# Soapbox_of.net
KiCad netlist of a schematic drawn in EAGLE
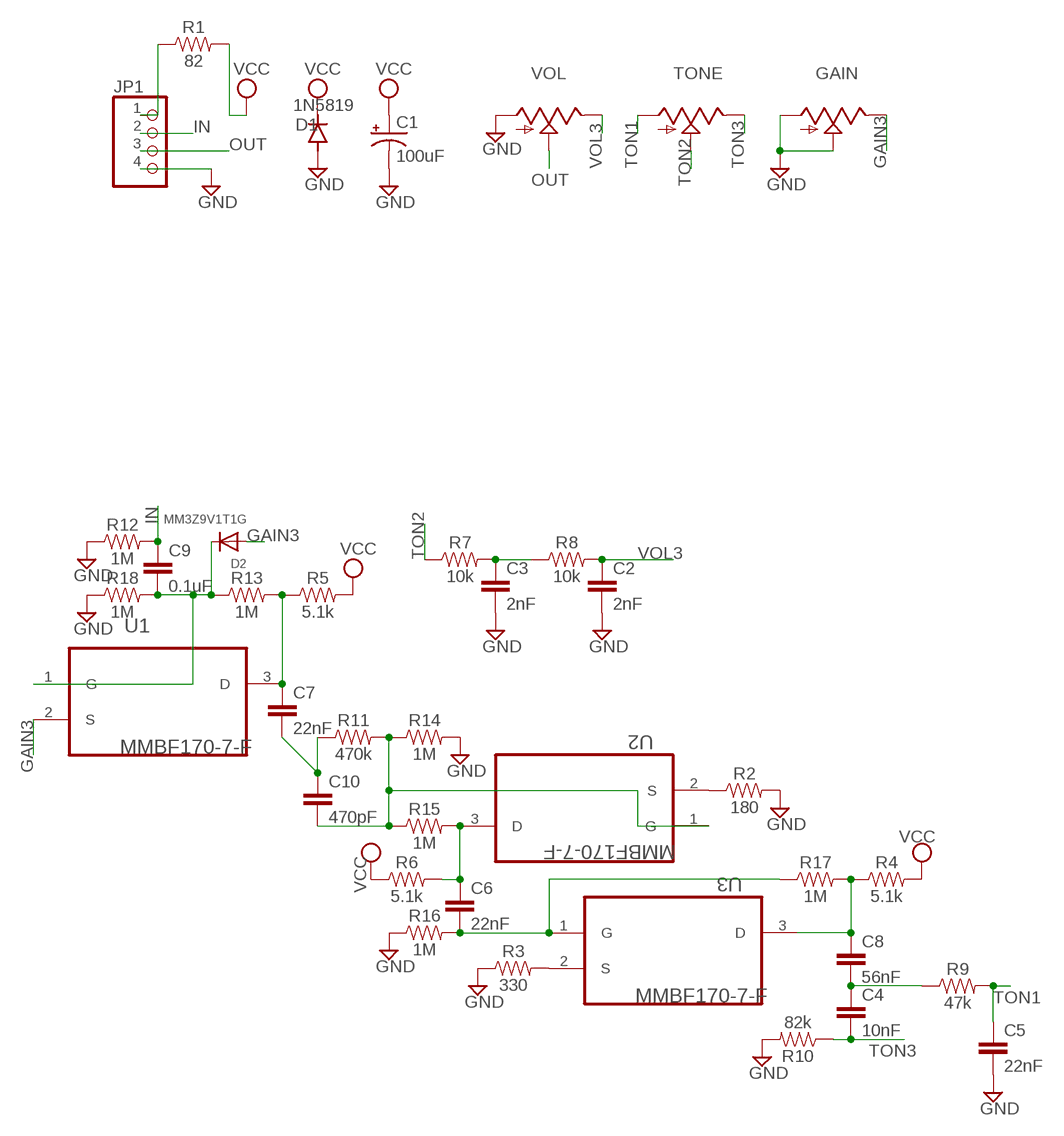
[diagram p0: schematic, sheet 1]

(export (version "E")
  (design (tool "Eeschema 10.0.6"))
  (components
    (comp (ref "C1")
      (value "100uF")
      (footprint "eagle-import:PAN_B_SMD+THRU")
      (libsource (lib "eagle-import") (part "CAP_SMD+THRUPAN_B"))
    )
    (comp (ref "C2")
      (value "2nF")
      (footprint "eagle-import:0603")
      (libsource (lib "eagle-import") (part "2.2NF/2200PF-0603-50V-10%"))
    )
    (comp (ref "C3")
      (value "2nF")
      (footprint "eagle-import:0603")
      (libsource (lib "eagle-import") (part "2.2NF/2200PF-0603-50V-10%"))
    )
    (comp (ref "C4")
      (value "10nF")
      (footprint "eagle-import:0603")
      (libsource (lib "eagle-import") (part "10NF-0603-50V-10%"))
    )
    (comp (ref "C5")
      (value "22nF")
      (footprint "eagle-import:0603")
      (libsource (lib "eagle-import") (part "22NF/22,000PF-0603-50V-10%"))
    )
    (comp (ref "C6")
      (value "22nF")
      (footprint "eagle-import:0603")
      (libsource (lib "eagle-import") (part "22NF/22,000PF-0603-50V-10%"))
    )
    (comp (ref "C7")
      (value "22nF")
      (footprint "eagle-import:0603")
      (libsource (lib "eagle-import") (part "22NF/22,000PF-0603-50V-10%"))
    )
    (comp (ref "C8")
      (value "56nF")
      (footprint "eagle-import:0603")
      (libsource (lib "eagle-import") (part "47NF-0603-25V-5%"))
    )
    (comp (ref "C9")
      (value "0.1uF")
      (footprint "eagle-import:0603")
      (libsource (lib "eagle-import") (part "0.1UF-0603-25V-(+80/-20%)"))
    )
    (comp (ref "C10")
      (value "470pF")
      (footprint "eagle-import:0603")
      (libsource (lib "eagle-import") (part "470PF-0603-50V-5%"))
    )
    (comp (ref "D1")
      (value "1N5819")
      (footprint "eagle-import:SOD123")
      (libsource (lib "eagle-import") (part "DIODE-SOD123"))
    )
    (comp (ref "D2")
      (value "MM3Z9V1T1G")
      (footprint "eagle-import:SOD-323F")
      (libsource (lib "eagle-import") (part "DIODESOD-323F"))
    )
    (comp (ref "GAIN")
      (value "9MM_SNAP-IN_POT_")
      (footprint "eagle-import:9MM_SNAP-IN_POT")
      (libsource (lib "eagle-import") (part "9MM_SNAP-IN_POT_"))
    )
    (comp (ref "JP1")
      (value "PINHD-1X4")
      (footprint "eagle-import:1X04")
      (libsource (lib "eagle-import") (part "PINHD-1X4"))
    )
    (comp (ref "R1")
      (value "82")
      (footprint "eagle-import:0603")
      (libsource (lib "eagle-import") (part "82OHM-0603-1/10W-1%"))
    )
    (comp (ref "R2")
      (value "180")
      (footprint "eagle-import:0603")
      (libsource (lib "eagle-import") (part "180OHM-0603-1/10W-1%"))
    )
    (comp (ref "R3")
      (value "330")
      (footprint "eagle-import:0603")
      (libsource (lib "eagle-import") (part "330OHM-0603-1/10W-1%"))
    )
    (comp (ref "R4")
      (value "5.1k")
      (footprint "eagle-import:0603")
      (libsource (lib "eagle-import") (part "5.6KOHM-0603-1/10W-1%"))
    )
    (comp (ref "R5")
      (value "5.1k")
      (footprint "eagle-import:0603")
      (libsource (lib "eagle-import") (part "5.6KOHM-0603-1/10W-1%"))
    )
    (comp (ref "R6")
      (value "5.1k")
      (footprint "eagle-import:0603")
      (libsource (lib "eagle-import") (part "5.6KOHM-0603-1/10W-1%"))
    )
    (comp (ref "R7")
      (value "10k")
      (footprint "eagle-import:0603")
      (libsource (lib "eagle-import") (part "10KOHM-0603-1/10W-1%"))
    )
    (comp (ref "R8")
      (value "10k")
      (footprint "eagle-import:0603")
      (libsource (lib "eagle-import") (part "10KOHM-0603-1/10W-1%"))
    )
    (comp (ref "R9")
      (value "47k")
      (footprint "eagle-import:0603")
      (libsource (lib "eagle-import") (part "47KOHM-0603-1/10W-1%"))
    )
    (comp (ref "R10")
      (value "82k")
      (footprint "eagle-import:0603")
      (libsource (lib "eagle-import") (part "82OHM-0603-1/10W-1%"))
    )
    (comp (ref "R11")
      (value "470k")
      (footprint "eagle-import:0603")
      (libsource (lib "eagle-import") (part "470OHM-0603-1/10W-1%"))
    )
    (comp (ref "R12")
      (value "1M")
      (footprint "eagle-import:0603")
      (libsource (lib "eagle-import") (part "1MOHM-0603-1/4W-5%"))
    )
    (comp (ref "R13")
      (value "1M")
      (footprint "eagle-import:0603")
      (libsource (lib "eagle-import") (part "1MOHM-0603-1/4W-5%"))
    )
    (comp (ref "R14")
      (value "1M")
      (footprint "eagle-import:0603")
      (libsource (lib "eagle-import") (part "1MOHM-0603-1/4W-5%"))
    )
    (comp (ref "R15")
      (value "1M")
      (footprint "eagle-import:0603")
      (libsource (lib "eagle-import") (part "1MOHM-0603-1/4W-5%"))
    )
    (comp (ref "R16")
      (value "1M")
      (footprint "eagle-import:0603")
      (libsource (lib "eagle-import") (part "1MOHM-0603-1/4W-5%"))
    )
    (comp (ref "R17")
      (value "1M")
      (footprint "eagle-import:0603")
      (libsource (lib "eagle-import") (part "1MOHM-0603-1/4W-5%"))
    )
    (comp (ref "R18")
      (value "1M")
      (footprint "eagle-import:0603")
      (libsource (lib "eagle-import") (part "1MOHM-0603-1/4W-5%"))
    )
    (comp (ref "TONE")
      (value "9MM_SNAP-IN_POT_")
      (footprint "eagle-import:9MM_SNAP-IN_POT")
      (libsource (lib "eagle-import") (part "9MM_SNAP-IN_POT_"))
    )
    (comp (ref "U1")
      (value "MMBF170-7-F")
      (footprint "eagle-import:SOT103P240X110-3N")
      (fields (field (name "MF") "Diodes Inc."))
      (libsource (lib "eagle-import") (part "MMBF170-7-F"))
    )
    (comp (ref "U2")
      (value "MMBF170-7-F")
      (footprint "eagle-import:SOT103P240X110-3N")
      (fields (field (name "MF") "Diodes Inc."))
      (libsource (lib "eagle-import") (part "MMBF170-7-F"))
    )
    (comp (ref "U3")
      (value "MMBF170-7-F")
      (footprint "eagle-import:SOT103P240X110-3N")
      (fields (field (name "MF") "Diodes Inc."))
      (libsource (lib "eagle-import") (part "MMBF170-7-F"))
    )
    (comp (ref "VOL")
      (value "9MM_SNAP-IN_POT_")
      (footprint "eagle-import:9MM_SNAP-IN_POT")
      (libsource (lib "eagle-import") (part "9MM_SNAP-IN_POT_"))
    )
  )
  (nets
    (net (code "1") (name "/GAIN3") (class "Default")
      (node (ref "D2") (pin "A") (pinfunction "A_A") (pintype "passive"))
      (node (ref "GAIN") (pin "3") (pinfunction "E_3") (pintype "passive"))
      (node (ref "U1") (pin "2") (pinfunction "S_2") (pintype "passive"))
    )
    (net (code "2") (name "/IN") (class "Default")
      (node (ref "C9") (pin "1") (pinfunction "1_1") (pintype "passive"))
      (node (ref "JP1") (pin "2") (pinfunction "2_2") (pintype "passive"))
      (node (ref "R12") (pin "2") (pinfunction "2_2") (pintype "passive"))
    )
    (net (code "3") (name "/OUT") (class "Default")
      (node (ref "JP1") (pin "3") (pinfunction "3_3") (pintype "passive"))
      (node (ref "VOL") (pin "2") (pinfunction "S_2") (pintype "passive"))
    )
    (net (code "4") (name "/TON1") (class "Default")
      (node (ref "C5") (pin "1") (pinfunction "1_1") (pintype "passive"))
      (node (ref "R9") (pin "2") (pinfunction "2_2") (pintype "passive"))
      (node (ref "TONE") (pin "1") (pinfunction "A_1") (pintype "passive"))
    )
    (net (code "5") (name "/TON2") (class "Default")
      (node (ref "R7") (pin "1") (pinfunction "1_1") (pintype "passive"))
      (node (ref "TONE") (pin "2") (pinfunction "S_2") (pintype "passive"))
    )
    (net (code "6") (name "/TON3") (class "Default")
      (node (ref "C4") (pin "2") (pinfunction "2_2") (pintype "passive"))
      (node (ref "R10") (pin "1") (pinfunction "1_1") (pintype "passive"))
      (node (ref "TONE") (pin "3") (pinfunction "E_3") (pintype "passive"))
    )
    (net (code "7") (name "/VOL3") (class "Default")
      (node (ref "C2") (pin "1") (pinfunction "1_1") (pintype "passive"))
      (node (ref "R8") (pin "2") (pinfunction "2_2") (pintype "passive"))
      (node (ref "VOL") (pin "3") (pinfunction "E_3") (pintype "passive"))
    )
    (net (code "8") (name "GND") (class "Default")
      (node (ref "C1") (pin "-") (pinfunction "-_-") (pintype "passive"))
      (node (ref "C1") (pin "--") (pinfunction "-_--") (pintype "passive"))
      (node (ref "C2") (pin "2") (pinfunction "2_2") (pintype "passive"))
      (node (ref "C3") (pin "2") (pinfunction "2_2") (pintype "passive"))
      (node (ref "C5") (pin "2") (pinfunction "2_2") (pintype "passive"))
      (node (ref "D1") (pin "A") (pinfunction "A_A") (pintype "passive"))
      (node (ref "GAIN") (pin "1") (pinfunction "A_1") (pintype "passive"))
      (node (ref "GAIN") (pin "2") (pinfunction "S_2") (pintype "passive"))
      (node (ref "JP1") (pin "4") (pinfunction "4_4") (pintype "passive"))
      (node (ref "R10") (pin "2") (pinfunction "2_2") (pintype "passive"))
      (node (ref "R12") (pin "1") (pinfunction "1_1") (pintype "passive"))
      (node (ref "R14") (pin "2") (pinfunction "2_2") (pintype "passive"))
      (node (ref "R16") (pin "1") (pinfunction "1_1") (pintype "passive"))
      (node (ref "R18") (pin "1") (pinfunction "1_1") (pintype "passive"))
      (node (ref "R2") (pin "2") (pinfunction "2_2") (pintype "passive"))
      (node (ref "R3") (pin "1") (pinfunction "1_1") (pintype "passive"))
      (node (ref "VOL") (pin "1") (pinfunction "A_1") (pintype "passive"))
    )
    (net (code "9") (name "Net-(C3-Pad1)") (class "Default")
      (node (ref "C3") (pin "1") (pinfunction "1_1") (pintype "passive"))
      (node (ref "R7") (pin "2") (pinfunction "2_2") (pintype "passive"))
      (node (ref "R8") (pin "1") (pinfunction "1_1") (pintype "passive"))
    )
    (net (code "10") (name "Net-(C4-Pad1)") (class "Default")
      (node (ref "C4") (pin "1") (pinfunction "1_1") (pintype "passive"))
      (node (ref "C8") (pin "2") (pinfunction "2_2") (pintype "passive"))
      (node (ref "R9") (pin "1") (pinfunction "1_1") (pintype "passive"))
    )
    (net (code "11") (name "Net-(C10-Pad1)") (class "Default")
      (node (ref "C10") (pin "1") (pinfunction "1_1") (pintype "passive"))
      (node (ref "C7") (pin "2") (pinfunction "2_2") (pintype "passive"))
      (node (ref "R11") (pin "1") (pinfunction "1_1") (pintype "passive"))
    )
    (net (code "12") (name "Net-(JP1-Pad1)") (class "Default")
      (node (ref "JP1") (pin "1") (pinfunction "1_1") (pintype "passive"))
      (node (ref "R1") (pin "1") (pinfunction "1_1") (pintype "passive"))
    )
    (net (code "13") (name "Net-(U1-D)") (class "Default")
      (node (ref "C7") (pin "1") (pinfunction "1_1") (pintype "passive"))
      (node (ref "R13") (pin "2") (pinfunction "2_2") (pintype "passive"))
      (node (ref "R5") (pin "1") (pinfunction "1_1") (pintype "passive"))
      (node (ref "U1") (pin "3") (pinfunction "D_3") (pintype "output"))
    )
    (net (code "14") (name "Net-(U1-G)") (class "Default")
      (node (ref "C9") (pin "2") (pinfunction "2_2") (pintype "passive"))
      (node (ref "D2") (pin "C") (pinfunction "C_C") (pintype "passive"))
      (node (ref "R13") (pin "1") (pinfunction "1_1") (pintype "passive"))
      (node (ref "R18") (pin "2") (pinfunction "2_2") (pintype "passive"))
      (node (ref "U1") (pin "1") (pinfunction "G_1") (pintype "input"))
    )
    (net (code "15") (name "Net-(U2-D)") (class "Default")
      (node (ref "C6") (pin "1") (pinfunction "1_1") (pintype "passive"))
      (node (ref "R15") (pin "2") (pinfunction "2_2") (pintype "passive"))
      (node (ref "R6") (pin "2") (pinfunction "2_2") (pintype "passive"))
      (node (ref "U2") (pin "3") (pinfunction "D_3") (pintype "output"))
    )
    (net (code "16") (name "Net-(U2-G)") (class "Default")
      (node (ref "C10") (pin "2") (pinfunction "2_2") (pintype "passive"))
      (node (ref "R11") (pin "2") (pinfunction "2_2") (pintype "passive"))
      (node (ref "R14") (pin "1") (pinfunction "1_1") (pintype "passive"))
      (node (ref "R15") (pin "1") (pinfunction "1_1") (pintype "passive"))
      (node (ref "U2") (pin "1") (pinfunction "G_1") (pintype "input"))
    )
    (net (code "17") (name "Net-(U2-S)") (class "Default")
      (node (ref "R2") (pin "1") (pinfunction "1_1") (pintype "passive"))
      (node (ref "U2") (pin "2") (pinfunction "S_2") (pintype "passive"))
    )
    (net (code "18") (name "Net-(U3-D)") (class "Default")
      (node (ref "C8") (pin "1") (pinfunction "1_1") (pintype "passive"))
      (node (ref "R17") (pin "2") (pinfunction "2_2") (pintype "passive"))
      (node (ref "R4") (pin "1") (pinfunction "1_1") (pintype "passive"))
      (node (ref "U3") (pin "3") (pinfunction "D_3") (pintype "output"))
    )
    (net (code "19") (name "Net-(U3-G)") (class "Default")
      (node (ref "C6") (pin "2") (pinfunction "2_2") (pintype "passive"))
      (node (ref "R16") (pin "2") (pinfunction "2_2") (pintype "passive"))
      (node (ref "R17") (pin "1") (pinfunction "1_1") (pintype "passive"))
      (node (ref "U3") (pin "1") (pinfunction "G_1") (pintype "input"))
    )
    (net (code "20") (name "Net-(U3-S)") (class "Default")
      (node (ref "R3") (pin "2") (pinfunction "2_2") (pintype "passive"))
      (node (ref "U3") (pin "2") (pinfunction "S_2") (pintype "passive"))
    )
    (net (code "21") (name "VCC") (class "Default")
      (node (ref "C1") (pin "+") (pinfunction "+_+") (pintype "passive"))
      (node (ref "C1") (pin "++") (pinfunction "+_++") (pintype "passive"))
      (node (ref "D1") (pin "C") (pinfunction "C_C") (pintype "passive"))
      (node (ref "R1") (pin "2") (pinfunction "2_2") (pintype "passive"))
      (node (ref "R4") (pin "2") (pinfunction "2_2") (pintype "passive"))
      (node (ref "R5") (pin "2") (pinfunction "2_2") (pintype "passive"))
      (node (ref "R6") (pin "1") (pinfunction "1_1") (pintype "passive"))
    )
  )
)
